# Isense.net
KiCad netlist of a schematic drawn in Altium Designer
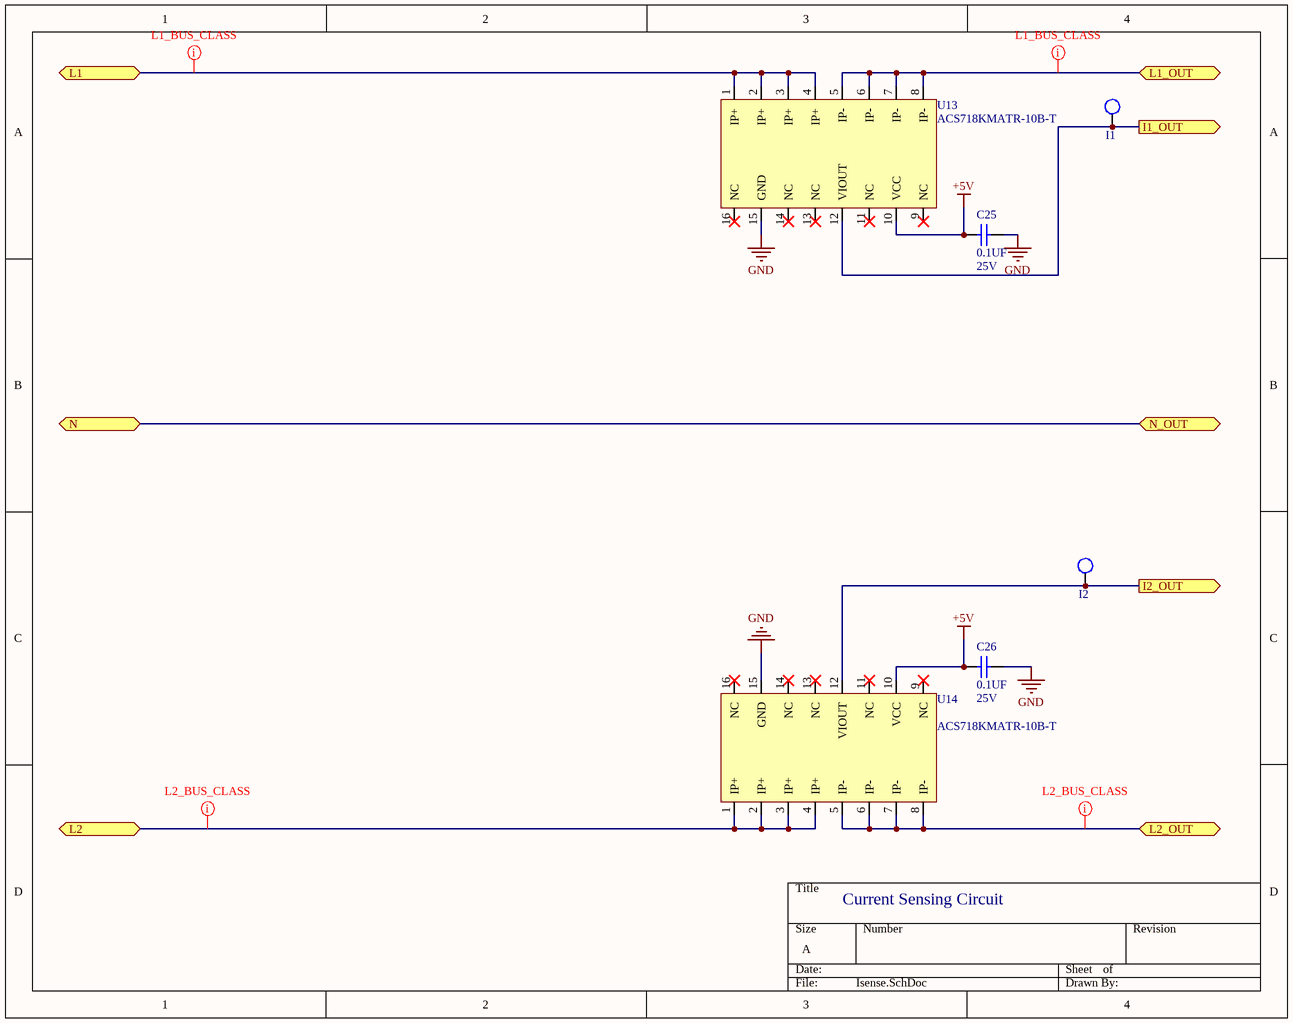
[diagram p0: Isense.SchDoc]

(export (version "E")
  (design (tool "Eeschema 10.0.6"))
  (components
    (comp (ref "C25")
      (value "GRM319R71E104KA01J")
      (footprint "CAPC3216X16N")
      (description "CAP CER 0.1UF 25V X7R 1206")
      (fields
        (field (name "MANUFACTURER") "Murata Electronics North America")
        (field (name "CAPACITANCE") "0.1UF")
        (field (name "VOLTAGE - RATED") "25V")
      )
      (libsource (lib "IntelligentJunctionBox") (part "GRM319R71E104KA01J"))
    )
    (comp (ref "C26")
      (value "GRM319R71E104KA01J")
      (footprint "CAPC3216X16N")
      (description "CAP CER 0.1UF 25V X7R 1206")
      (fields
        (field (name "MANUFACTURER") "Murata Electronics North America")
        (field (name "CAPACITANCE") "0.1UF")
        (field (name "VOLTAGE - RATED") "25V")
      )
      (libsource (lib "IntelligentJunctionBox") (part "GRM319R71E104KA01J"))
    )
    (comp (ref "I1")
      (value "Testpoint")
      (footprint "Testpoint")
      (libsource (lib "IntelligentJunctionBox") (part "Testpoint"))
    )
    (comp (ref "I2")
      (value "Testpoint")
      (footprint "Testpoint")
      (libsource (lib "IntelligentJunctionBox") (part "Testpoint"))
    )
    (comp (ref "U13")
      (value "ACS718KMATR-10B-T")
      (footprint "SOIC127P1030X265-16N")
      (description "SENSOR CURRENT HALL 10A AC/DC")
      (fields (field (name "MANUFACTURER") "Allegro MicroSystems, LLC"))
      (libsource (lib "IntelligentJunctionBox") (part "ACS718KMATR-10B-T"))
    )
    (comp (ref "U14")
      (value "ACS718KMATR-10B-T")
      (footprint "SOIC127P1030X265-16N")
      (description "SENSOR CURRENT HALL 10A AC/DC")
      (fields (field (name "MANUFACTURER") "Allegro MicroSystems, LLC"))
      (libsource (lib "") (part "ACS718KMATR-10B-T_1"))
    )
  )
  (nets
    (net (code "1") (name "+5V") (class "Default")
      (node (ref "C25") (pin "1") (pinfunction "1_1") (pintype "passive"))
      (node (ref "C26") (pin "1") (pinfunction "1_1") (pintype "passive"))
      (node (ref "U13") (pin "10") (pinfunction "VCC_10") (pintype "passive"))
      (node (ref "U14") (pin "10") (pinfunction "VCC_10") (pintype "passive"))
    )
    (net (code "2") (name "/I1_OUT") (class "Default")
      (node (ref "I1") (pin "1") (pinfunction "TP_1") (pintype "passive"))
      (node (ref "U13") (pin "12") (pinfunction "VIOUT_12") (pintype "passive"))
    )
    (net (code "3") (name "/I2_OUT") (class "Default")
      (node (ref "I2") (pin "1") (pinfunction "TP_1") (pintype "passive"))
      (node (ref "U14") (pin "12") (pinfunction "VIOUT_12") (pintype "passive"))
    )
    (net (code "4") (name "/L1") (class "Default")
      (node (ref "U13") (pin "1") (pinfunction "IP+_1") (pintype "passive"))
      (node (ref "U13") (pin "2") (pinfunction "IP+_2") (pintype "passive"))
      (node (ref "U13") (pin "3") (pinfunction "IP+_3") (pintype "passive"))
      (node (ref "U13") (pin "4") (pinfunction "IP+_4") (pintype "passive"))
    )
    (net (code "5") (name "/L1_OUT") (class "Default")
      (node (ref "U13") (pin "5") (pinfunction "IP-_5") (pintype "passive"))
      (node (ref "U13") (pin "6") (pinfunction "IP-_6") (pintype "passive"))
      (node (ref "U13") (pin "7") (pinfunction "IP-_7") (pintype "passive"))
      (node (ref "U13") (pin "8") (pinfunction "IP-_8") (pintype "passive"))
    )
    (net (code "6") (name "/L2") (class "Default")
      (node (ref "U14") (pin "1") (pinfunction "IP+_1") (pintype "passive"))
      (node (ref "U14") (pin "2") (pinfunction "IP+_2") (pintype "passive"))
      (node (ref "U14") (pin "3") (pinfunction "IP+_3") (pintype "passive"))
      (node (ref "U14") (pin "4") (pinfunction "IP+_4") (pintype "passive"))
    )
    (net (code "7") (name "/L2_OUT") (class "Default")
      (node (ref "U14") (pin "5") (pinfunction "IP-_5") (pintype "passive"))
      (node (ref "U14") (pin "6") (pinfunction "IP-_6") (pintype "passive"))
      (node (ref "U14") (pin "7") (pinfunction "IP-_7") (pintype "passive"))
      (node (ref "U14") (pin "8") (pinfunction "IP-_8") (pintype "passive"))
    )
    (net (code "9") (name "GND") (class "Default")
      (node (ref "C25") (pin "2") (pinfunction "2_2") (pintype "passive"))
      (node (ref "C26") (pin "2") (pinfunction "2_2") (pintype "passive"))
      (node (ref "U13") (pin "15") (pinfunction "GND_15") (pintype "passive"))
      (node (ref "U14") (pin "15") (pinfunction "GND_15") (pintype "passive"))
    )
    (net (code "10") (name "unconnected-(U13-NC-Pad9)") (class "Default")
      (node (ref "U13") (pin "9") (pinfunction "NC_9") (pintype "passive+no_connect"))
    )
    (net (code "11") (name "unconnected-(U13-NC-Pad11)") (class "Default")
      (node (ref "U13") (pin "11") (pinfunction "NC_11") (pintype "passive+no_connect"))
    )
    (net (code "12") (name "unconnected-(U13-NC-Pad13)") (class "Default")
      (node (ref "U13") (pin "13") (pinfunction "NC_13") (pintype "passive+no_connect"))
    )
    (net (code "13") (name "unconnected-(U13-NC-Pad14)") (class "Default")
      (node (ref "U13") (pin "14") (pinfunction "NC_14") (pintype "passive+no_connect"))
    )
    (net (code "14") (name "unconnected-(U13-NC-Pad16)") (class "Default")
      (node (ref "U13") (pin "16") (pinfunction "NC_16") (pintype "passive+no_connect"))
    )
    (net (code "15") (name "unconnected-(U14-NC-Pad9)") (class "Default")
      (node (ref "U14") (pin "9") (pinfunction "NC_9") (pintype "passive+no_connect"))
    )
    (net (code "16") (name "unconnected-(U14-NC-Pad11)") (class "Default")
      (node (ref "U14") (pin "11") (pinfunction "NC_11") (pintype "passive+no_connect"))
    )
    (net (code "17") (name "unconnected-(U14-NC-Pad13)") (class "Default")
      (node (ref "U14") (pin "13") (pinfunction "NC_13") (pintype "passive+no_connect"))
    )
    (net (code "18") (name "unconnected-(U14-NC-Pad14)") (class "Default")
      (node (ref "U14") (pin "14") (pinfunction "NC_14") (pintype "passive+no_connect"))
    )
    (net (code "19") (name "unconnected-(U14-NC-Pad16)") (class "Default")
      (node (ref "U14") (pin "16") (pinfunction "NC_16") (pintype "passive+no_connect"))
    )
  )
)
